# AmphenolPowerBreakout.net
KiCad netlist of a schematic drawn in Altium Designer
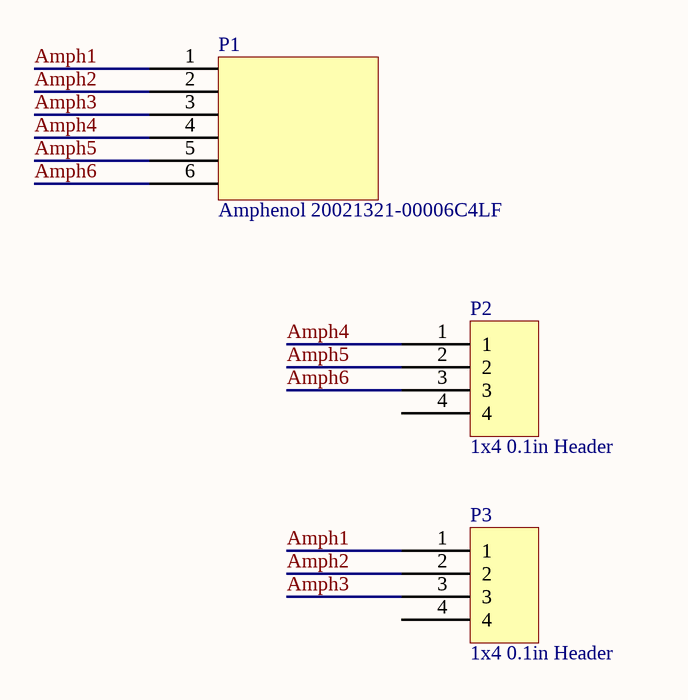
[diagram p0: AmphenolPowerBreakout.SchDoc]

(export (version "E")
  (design (tool "Eeschema 10.0.6"))
  (components
    (comp (ref "P1")
      (value "Amphenol 20021321-00006C4LF")
      (footprint "Amphenol FCI 20021321-00006C4LF - duplicate")
      (description "6 Position Receptacle Connector 0.050\" (1.27mm) Surface Mount Gold")
      (libsource (lib "SubjuGator8") (part "Amphenol FCI 20021321-00006C4LF"))
    )
    (comp (ref "P2")
      (value "1x4 0.1in Header")
      (footprint "1x4 0.1in Header")
      (libsource (lib "SubjuGator8") (part "1x4 0.1in Header"))
    )
    (comp (ref "P3")
      (value "1x4 0.1in Header")
      (footprint "1x4 0.1in Header")
      (libsource (lib "SubjuGator8") (part "1x4 0.1in Header"))
    )
  )
  (nets
    (net (code "1") (name "/Amph1") (class "Default")
      (node (ref "P1") (pin "1") (pintype "passive"))
      (node (ref "P3") (pin "1") (pinfunction "1_1") (pintype "passive"))
    )
    (net (code "2") (name "/Amph2") (class "Default")
      (node (ref "P1") (pin "2") (pintype "passive"))
      (node (ref "P3") (pin "2") (pinfunction "2_2") (pintype "passive"))
    )
    (net (code "3") (name "/Amph3") (class "Default")
      (node (ref "P1") (pin "3") (pintype "passive"))
      (node (ref "P3") (pin "3") (pinfunction "3_3") (pintype "passive"))
    )
    (net (code "4") (name "/Amph4") (class "Default")
      (node (ref "P1") (pin "4") (pintype "passive"))
      (node (ref "P2") (pin "1") (pinfunction "1_1") (pintype "passive"))
    )
    (net (code "5") (name "/Amph5") (class "Default")
      (node (ref "P1") (pin "5") (pintype "passive"))
      (node (ref "P2") (pin "2") (pinfunction "2_2") (pintype "passive"))
    )
    (net (code "6") (name "/Amph6") (class "Default")
      (node (ref "P1") (pin "6") (pintype "passive"))
      (node (ref "P2") (pin "3") (pinfunction "3_3") (pintype "passive"))
    )
    (net (code "7") (name "unconnected-(P2-Pad4)") (class "Default")
      (node (ref "P2") (pin "4") (pinfunction "4_4") (pintype "passive"))
    )
    (net (code "8") (name "unconnected-(P3-Pad4)") (class "Default")
      (node (ref "P3") (pin "4") (pinfunction "4_4") (pintype "passive"))
    )
  )
)
